# Molex_Conn.net
KiCad netlist of a schematic drawn in Altium Designer
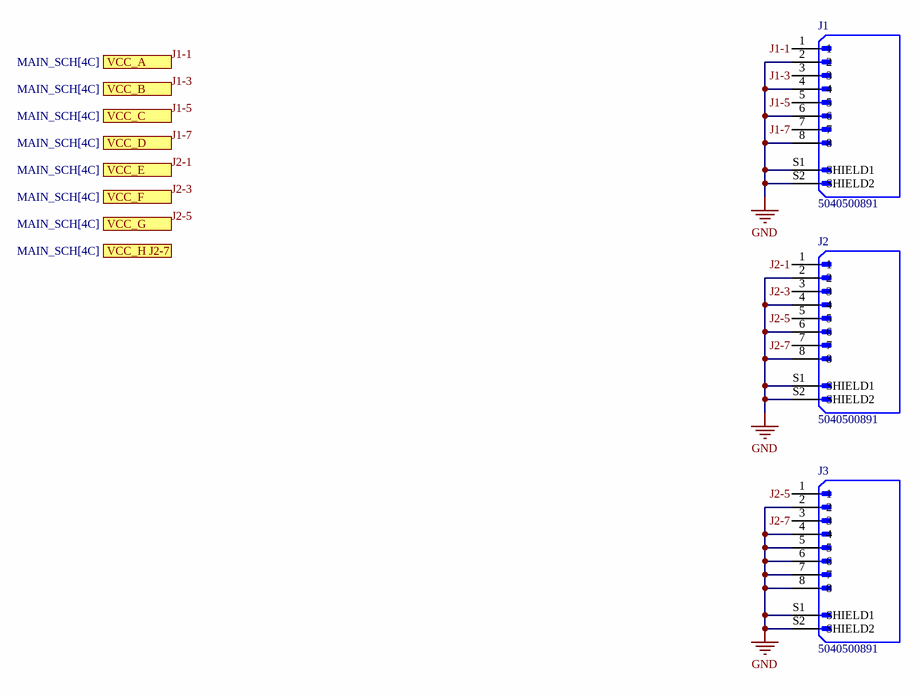
[diagram p0: Molex_Conn.SchDoc]

(export (version "E")
  (design (tool "Eeschema 10.0.6"))
  (components
    (comp (ref "J1")
      (value "5040500891")
      (footprint "MOLEX_5040500891")
      (libsource (lib "5040500891") (part "5040500891"))
    )
    (comp (ref "J2")
      (value "5040500891")
      (footprint "MOLEX_5040500891")
      (libsource (lib "5040500891") (part "5040500891"))
    )
    (comp (ref "J3")
      (value "5040500891")
      (footprint "MOLEX_5040500891")
      (libsource (lib "5040500891") (part "5040500891"))
    )
  )
  (nets
    (net (code "1") (name "/J1-1") (class "Default")
      (node (ref "J1") (pin "1") (pinfunction "1_1") (pintype "passive"))
    )
    (net (code "2") (name "/J1-3") (class "Default")
      (node (ref "J1") (pin "3") (pinfunction "3_3") (pintype "passive"))
    )
    (net (code "3") (name "/J1-5") (class "Default")
      (node (ref "J1") (pin "5") (pinfunction "5_5") (pintype "passive"))
    )
    (net (code "4") (name "/J1-7") (class "Default")
      (node (ref "J1") (pin "7") (pinfunction "7_7") (pintype "passive"))
    )
    (net (code "5") (name "/J2-1") (class "Default")
      (node (ref "J2") (pin "1") (pinfunction "1_1") (pintype "passive"))
    )
    (net (code "6") (name "/J2-3") (class "Default")
      (node (ref "J2") (pin "3") (pinfunction "3_3") (pintype "passive"))
    )
    (net (code "7") (name "/J2-5") (class "Default")
      (node (ref "J2") (pin "5") (pinfunction "5_5") (pintype "passive"))
      (node (ref "J3") (pin "1") (pinfunction "1_1") (pintype "passive"))
    )
    (net (code "8") (name "/J2-7") (class "Default")
      (node (ref "J2") (pin "7") (pinfunction "7_7") (pintype "passive"))
      (node (ref "J3") (pin "3") (pinfunction "3_3") (pintype "passive"))
    )
    (net (code "9") (name "GND") (class "Default")
      (node (ref "J1") (pin "2") (pinfunction "2_2") (pintype "passive"))
      (node (ref "J1") (pin "4") (pinfunction "4_4") (pintype "passive"))
      (node (ref "J1") (pin "6") (pinfunction "6_6") (pintype "passive"))
      (node (ref "J1") (pin "8") (pinfunction "8_8") (pintype "passive"))
      (node (ref "J1") (pin "S1") (pinfunction "SHIELD1_S1") (pintype "passive"))
      (node (ref "J1") (pin "S2") (pinfunction "SHIELD2_S2") (pintype "passive"))
      (node (ref "J2") (pin "2") (pinfunction "2_2") (pintype "passive"))
      (node (ref "J2") (pin "4") (pinfunction "4_4") (pintype "passive"))
      (node (ref "J2") (pin "6") (pinfunction "6_6") (pintype "passive"))
      (node (ref "J2") (pin "8") (pinfunction "8_8") (pintype "passive"))
      (node (ref "J2") (pin "S1") (pinfunction "SHIELD1_S1") (pintype "passive"))
      (node (ref "J2") (pin "S2") (pinfunction "SHIELD2_S2") (pintype "passive"))
      (node (ref "J3") (pin "2") (pinfunction "2_2") (pintype "passive"))
      (node (ref "J3") (pin "4") (pinfunction "4_4") (pintype "passive"))
      (node (ref "J3") (pin "5") (pinfunction "5_5") (pintype "passive"))
      (node (ref "J3") (pin "6") (pinfunction "6_6") (pintype "passive"))
      (node (ref "J3") (pin "7") (pinfunction "7_7") (pintype "passive"))
      (node (ref "J3") (pin "8") (pinfunction "8_8") (pintype "passive"))
      (node (ref "J3") (pin "S1") (pinfunction "SHIELD1_S1") (pintype "passive"))
      (node (ref "J3") (pin "S2") (pinfunction "SHIELD2_S2") (pintype "passive"))
    )
  )
)
